# Sheet1chinh_thuc_2.net
KiCad netlist of a schematic drawn in Altium Designer
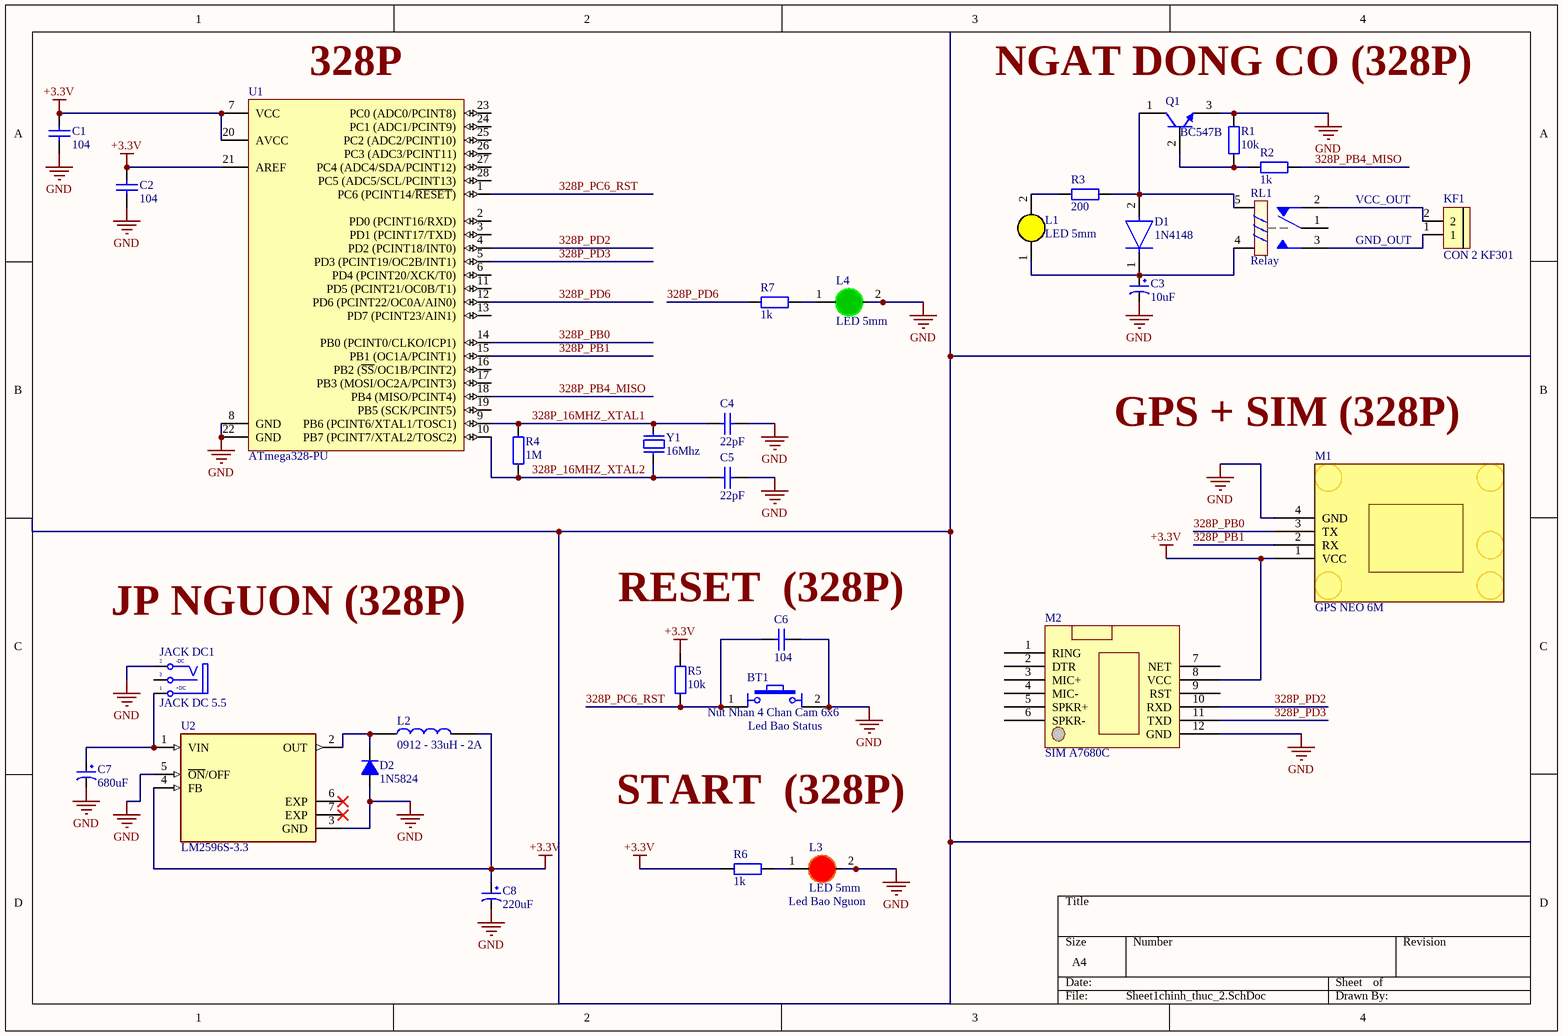
[diagram p0: Sheet1chinh_thuc_2.SchDoc]

(export (version "E")
  (design (tool "Eeschema 10.0.6"))
  (components
    (comp (ref "BT1")
      (value "Nut Nhan 4 Chan Cam 6x6")
      (footprint "Nut Nhan 4 Chan Cam 6x6")
      (description "Nut Nhan 4 Chan 6x6mm")
      (libsource (lib "Altium_Lib_by_KhueNguyenCreator") (part "Nut Nhan 4 Chan Cam 6x6"))
    )
    (comp (ref "C1")
      (value "104")
      (footprint "tu gom")
      (description "Cắm")
      (libsource (lib "Altium_Lib_by_KhueNguyenCreator") (part "Tu gom 104 50V"))
    )
    (comp (ref "C2")
      (value "104")
      (footprint "tu gom")
      (description "Cắm")
      (libsource (lib "Altium_Lib_by_KhueNguyenCreator") (part "Tu gom 104 50V"))
    )
    (comp (ref "C3")
      (value "10uF")
      (footprint "tu hoa 4mm")
      (description "Cắm")
      (libsource (lib "Altium_Lib_by_KhueNguyenCreator") (part "Tu Hoa 10uF 25V 4x7"))
    )
    (comp (ref "C4")
      (value "22pF")
      (footprint "tu gom")
      (description "Cắm")
      (libsource (lib "Altium_Lib_by_KhueNguyenCreator") (part "Tu gom 22pF 50V"))
    )
    (comp (ref "C5")
      (value "22pF")
      (footprint "tu gom")
      (description "Cắm")
      (libsource (lib "Altium_Lib_by_KhueNguyenCreator") (part "Tu gom 22pF 50V"))
    )
    (comp (ref "C6")
      (value "104")
      (footprint "tu gom")
      (description "Cắm")
      (libsource (lib "Altium_Lib_by_KhueNguyenCreator") (part "Tu gom 104 50V"))
    )
    (comp (ref "C7")
      (value "680uF")
      (footprint "tu hoa 13mm")
      (description "Cắm")
      (libsource (lib "Altium_Lib_by_KhueNguyenCreator") (part "Tu Hoa 680uF 25V 13x17"))
    )
    (comp (ref "C8")
      (value "220uF")
      (footprint "Tu hoa 8mm")
      (description "Cắm")
      (libsource (lib "Altium_Lib_by_KhueNguyenCreator") (part "Tu Hoa 220uF 25V 8x10"))
    )
    (comp (ref "D1")
      (value "1N4148")
      (footprint "FP-017AG-MFG")
      (description "DIODE GEN PURP 100V 200MA DO35")
      (fields (field (name "VOLTAGE") "100V"))
      (libsource (lib "Components - 29.11.24 - 08.09") (part "CMP-07163-000046-1"))
    )
    (comp (ref "D2")
      (value "1N5824")
      (footprint "DIODE 0.5A")
      (description "Cắm")
      (libsource (lib "Altium_Lib_by_KhueNguyenCreator") (part "Diode 1N4148"))
    )
    (comp (ref "JACK DC1")
      (value "JACK DC 5.5")
      (footprint "JACK DC 5.5")
      (libsource (lib "Altium_Lib_by_KhueNguyenCreator") (part "JACK DC 5.5"))
    )
    (comp (ref "KF1")
      (value "CON 2 KF301")
      (footprint "Con 2 KF301 5.08")
      (description "Cắm")
      (libsource (lib "Altium_Lib_by_KhueNguyenCreator") (part "CON 2 KF301"))
    )
    (comp (ref "L1")
      (value "LED 5mm")
      (footprint "LED-5MM-Yellow")
      (description "Cắm")
      (libsource (lib "Altium_Lib_by_KhueNguyenCreator") (part "LED 5mm Vang"))
    )
    (comp (ref "L2")
      (value "0912 - 33uH - 2A")
      (footprint "CUON CAM 100uH3A")
      (description "Cắm")
      (libsource (lib "Altium_Lib_by_KhueNguyenCreator") (part "CUON CAM 470uH DIP"))
    )
    (comp (ref "L3")
      (value "LED 5mm")
      (footprint "LED-5MM-RED")
      (description "Cắm")
      (libsource (lib "Altium_Lib_by_KhueNguyenCreator") (part "LED 5mm Do"))
    )
    (comp (ref "L4")
      (value "LED 5mm")
      (footprint "LED-5MM-Green")
      (description "Cắm")
      (libsource (lib "Altium_Lib_by_KhueNguyenCreator") (part "LED 5mm Xanh La"))
    )
    (comp (ref "M1")
      (value "GPS NEO 6M")
      (footprint "PCBComponent_1")
      (libsource (lib "Integrated_Library1") (part "GPS NEO 6M"))
    )
    (comp (ref "M2")
      (value "SIM A7680C")
      (footprint "PCBComponent_1")
      (libsource (lib "Integrated_Library1") (part "SIM A7680C"))
    )
    (comp (ref "Q1")
      (value "BC547B")
      (footprint "ONSC-TO-92-3-29-11")
      (description "Amplifier Transistor, NPN Silicon, 3-Pin TO-92, Bulk Box")
      (fields (field (name "MANUFACTURER") "On Semiconductor"))
      (libsource (lib "Components - 29.11.24 - 08.11") (part "CMP-1048-01467-1"))
    )
    (comp (ref "R1")
      (value "10k")
      (footprint "tro vach 1/2w")
      (description "Cắm")
      (libsource (lib "Altium_Lib_by_KhueNguyenCreator") (part "Tro Vach 1/2W 5% 10k"))
    )
    (comp (ref "R2")
      (value "1k")
      (footprint "tro vach 1/2w")
      (description "Cắm")
      (libsource (lib "Altium_Lib_by_KhueNguyenCreator") (part "Tro Vach 1/2W 5% 1k"))
    )
    (comp (ref "R3")
      (value "200")
      (footprint "tro vach 1/2w")
      (description "Cắm")
      (libsource (lib "Altium_Lib_by_KhueNguyenCreator") (part "Tro Vach 1/2W 5% 150R"))
    )
    (comp (ref "R4")
      (value "1M")
      (footprint "tro vach 1/2w")
      (description "Cắm")
      (libsource (lib "Altium_Lib_by_KhueNguyenCreator") (part "Tro Vach 1/2W 5% 1M"))
    )
    (comp (ref "R5")
      (value "10k")
      (footprint "tro vach 1/2w")
      (description "Cắm")
      (libsource (lib "Altium_Lib_by_KhueNguyenCreator") (part "Tro Vach 1/2W 5% 10k"))
    )
    (comp (ref "R6")
      (value "1k")
      (footprint "tro vach 1/2w")
      (description "Cắm")
      (libsource (lib "Altium_Lib_by_KhueNguyenCreator") (part "Tro Vach 1/2W 5% 1k"))
    )
    (comp (ref "R7")
      (value "1k")
      (footprint "tro vach 1/2w")
      (description "Cắm")
      (libsource (lib "Altium_Lib_by_KhueNguyenCreator") (part "Tro Vach 1/2W 5% 1k"))
    )
    (comp (ref "RL1")
      (value "Relay")
      (footprint "Relay 5 Chan SRD")
      (description "Relay 5 Chan")
      (libsource (lib "Altium_Lib_by_KhueNguyenCreator") (part "Relay 5 Chan SRD"))
    )
    (comp (ref "U1")
      (value "ATmega328-PU")
      (footprint "28P3")
      (libsource (lib "Altium_Lib_by_KhueNguyenCreator") (part "CMP-0095-00015-2"))
    )
    (comp (ref "U2")
      (value "LM2596S-3.3")
      (footprint "VREG_LM2596S-3.3")
      (description "SIMPLE SWITCHER&reg; 4.5V to 40V, 3A Low Component Count Step-Down Regulator 5-DDPAK/TO-263")
      (fields (field (name "MF") "Texas Instruments"))
      (libsource (lib "LM2596S-3.3") (part "LM2596S-3.3"))
    )
    (comp (ref "Y1")
      (value "16Mhz")
      (footprint "Thach Anh 2 chan cam")
      (description "Crystal For all Crystal 2pin.")
      (libsource (lib "Altium_Lib_by_KhueNguyenCreator") (part "Thach Anh 2 chan Cam"))
    )
  )
  (nets
    (net (code "1") (name "+3.3V") (class "Default")
      (node (ref "C1") (pin "1") (pinfunction "1_1") (pintype "passive"))
      (node (ref "C2") (pin "1") (pinfunction "1_1") (pintype "passive"))
      (node (ref "C8") (pin "1") (pinfunction "1_1") (pintype "passive"))
      (node (ref "L2") (pin "2") (pinfunction "2_2") (pintype "passive"))
      (node (ref "M1") (pin "1") (pinfunction "VCC_1") (pintype "passive"))
      (node (ref "M2") (pin "8") (pinfunction "VCC_8") (pintype "passive"))
      (node (ref "R5") (pin "2") (pinfunction "2_2") (pintype "passive"))
      (node (ref "R6") (pin "1") (pinfunction "1_1") (pintype "passive"))
      (node (ref "U1") (pin "20") (pinfunction "AVCC_20") (pintype "power_in"))
      (node (ref "U1") (pin "21") (pinfunction "AREF_21") (pintype "power_in"))
      (node (ref "U1") (pin "7") (pinfunction "VCC_7") (pintype "power_in"))
      (node (ref "U2") (pin "4") (pinfunction "FB_4") (pintype "input"))
    )
    (net (code "2") (name "/328P_16MHZ_XTAL1") (class "Default")
      (node (ref "C4") (pin "2") (pinfunction "2_2") (pintype "passive"))
      (node (ref "R4") (pin "2") (pinfunction "2_2") (pintype "passive"))
      (node (ref "U1") (pin "9") (pinfunction "PB6_(PCINT6/XTAL1/TOSC1)_9") (pintype "bidirectional"))
      (node (ref "Y1") (pin "2") (pinfunction "2_2") (pintype "passive"))
    )
    (net (code "3") (name "/328P_16MHZ_XTAL2") (class "Default")
      (node (ref "C5") (pin "2") (pinfunction "2_2") (pintype "passive"))
      (node (ref "R4") (pin "1") (pinfunction "1_1") (pintype "passive"))
      (node (ref "U1") (pin "10") (pinfunction "PB7_(PCINT7/XTAL2/TOSC2)_10") (pintype "bidirectional"))
      (node (ref "Y1") (pin "1") (pinfunction "1_1") (pintype "passive"))
    )
    (net (code "4") (name "/328P_PB0") (class "Default")
      (node (ref "M1") (pin "3") (pinfunction "TX_3") (pintype "passive"))
      (node (ref "U1") (pin "14") (pinfunction "PB0_(PCINT0/CLKO/ICP1)_14") (pintype "bidirectional"))
    )
    (net (code "5") (name "/328P_PB1") (class "Default")
      (node (ref "M1") (pin "2") (pinfunction "RX_2") (pintype "passive"))
      (node (ref "U1") (pin "15") (pinfunction "PB1_(OC1A/PCINT1)_15") (pintype "bidirectional"))
    )
    (net (code "6") (name "/328P_PB4_MISO") (class "Default")
      (node (ref "R2") (pin "2") (pinfunction "2_2") (pintype "passive"))
      (node (ref "U1") (pin "18") (pinfunction "PB4_(MISO/PCINT4)_18") (pintype "bidirectional"))
    )
    (net (code "7") (name "/328P_PC6_RST") (class "Default")
      (node (ref "BT1") (pin "1") (pintype "passive"))
      (node (ref "C6") (pin "2") (pinfunction "2_2") (pintype "passive"))
      (node (ref "R5") (pin "1") (pinfunction "1_1") (pintype "passive"))
      (node (ref "U1") (pin "1") (pinfunction "PC6_(PCINT14/~{RESET})_1") (pintype "bidirectional"))
    )
    (net (code "8") (name "/328P_PD2") (class "Default")
      (node (ref "M2") (pin "10") (pinfunction "RXD_10") (pintype "passive"))
      (node (ref "U1") (pin "4") (pinfunction "PD2_(PCINT18/INT0)_4") (pintype "bidirectional"))
    )
    (net (code "9") (name "/328P_PD3") (class "Default")
      (node (ref "M2") (pin "11") (pinfunction "TXD_11") (pintype "passive"))
      (node (ref "U1") (pin "5") (pinfunction "PD3_(PCINT19/OC2B/INT1)_5") (pintype "bidirectional"))
    )
    (net (code "10") (name "/328P_PD6") (class "Default")
      (node (ref "R7") (pin "1") (pinfunction "1_1") (pintype "passive"))
      (node (ref "U1") (pin "12") (pinfunction "PD6_(PCINT22/OC0A/AIN0)_12") (pintype "bidirectional"))
    )
    (net (code "11") (name "GND") (class "Default")
      (node (ref "BT1") (pin "2") (pintype "passive"))
      (node (ref "C1") (pin "2") (pinfunction "2_2") (pintype "passive"))
      (node (ref "C2") (pin "2") (pinfunction "2_2") (pintype "passive"))
      (node (ref "C3") (pin "2") (pinfunction "2_2") (pintype "passive"))
      (node (ref "C4") (pin "1") (pinfunction "1_1") (pintype "passive"))
      (node (ref "C5") (pin "1") (pinfunction "1_1") (pintype "passive"))
      (node (ref "C6") (pin "1") (pinfunction "1_1") (pintype "passive"))
      (node (ref "C7") (pin "2") (pinfunction "2_2") (pintype "passive"))
      (node (ref "C8") (pin "2") (pinfunction "2_2") (pintype "passive"))
      (node (ref "D2") (pin "1") (pinfunction "A_1") (pintype "passive"))
      (node (ref "JACK DC1") (pin "2") (pinfunction "TN_2") (pintype "passive"))
      (node (ref "L3") (pin "2") (pinfunction "K_2") (pintype "passive"))
      (node (ref "L4") (pin "2") (pinfunction "K_2") (pintype "passive"))
      (node (ref "M1") (pin "4") (pinfunction "GND_4") (pintype "passive"))
      (node (ref "M2") (pin "12") (pinfunction "GND_12") (pintype "passive"))
      (node (ref "Q1") (pin "3") (pinfunction "E_3") (pintype "passive"))
      (node (ref "R1") (pin "2") (pinfunction "2_2") (pintype "passive"))
      (node (ref "U1") (pin "22") (pinfunction "GND_22") (pintype "power_in"))
      (node (ref "U1") (pin "8") (pinfunction "GND_8") (pintype "power_in"))
      (node (ref "U2") (pin "3") (pinfunction "GND_3") (pintype "power_in"))
      (node (ref "U2") (pin "5") (pinfunction "~{ON}/OFF_5") (pintype "input"))
    )
    (net (code "12") (name "Net-(D1-A)") (class "Default")
      (node (ref "D1") (pin "2") (pinfunction "A_2") (pintype "passive"))
      (node (ref "Q1") (pin "1") (pinfunction "C_1") (pintype "passive"))
      (node (ref "R3") (pin "2") (pinfunction "2_2") (pintype "passive"))
      (node (ref "RL1") (pin "5") (pinfunction "5_5") (pintype "passive"))
    )
    (net (code "13") (name "Net-(D1-C)") (class "Default")
      (node (ref "C3") (pin "1") (pinfunction "1_1") (pintype "passive"))
      (node (ref "D1") (pin "1") (pinfunction "C_1") (pintype "passive"))
      (node (ref "L1") (pin "1") (pinfunction "A_1") (pintype "passive"))
      (node (ref "RL1") (pin "4") (pinfunction "4_4") (pintype "passive"))
    )
    (net (code "14") (name "Net-(D2-K)") (class "Default")
      (node (ref "D2") (pin "2") (pinfunction "K_2") (pintype "passive"))
      (node (ref "L2") (pin "1") (pinfunction "1_1") (pintype "passive"))
      (node (ref "U2") (pin "2") (pinfunction "OUT_2") (pintype "output"))
    )
    (net (code "15") (name "Net-(JACK DC1-T)") (class "Default")
      (node (ref "C7") (pin "1") (pinfunction "1_1") (pintype "passive"))
      (node (ref "JACK DC1") (pin "1") (pinfunction "T_1") (pintype "passive"))
      (node (ref "U2") (pin "1") (pinfunction "VIN_1") (pintype "input"))
    )
    (net (code "16") (name "Net-(KF1-Pad1)") (class "Default")
      (node (ref "KF1") (pin "1") (pinfunction "1_1") (pintype "passive"))
      (node (ref "RL1") (pin "3") (pinfunction "3_3") (pintype "passive"))
    )
    (net (code "17") (name "Net-(KF1-Pad2)") (class "Default")
      (node (ref "KF1") (pin "2") (pinfunction "2_2") (pintype "passive"))
      (node (ref "RL1") (pin "2") (pinfunction "2_2") (pintype "passive"))
    )
    (net (code "18") (name "Net-(L1-K)") (class "Default")
      (node (ref "L1") (pin "2") (pinfunction "K_2") (pintype "passive"))
      (node (ref "R3") (pin "1") (pinfunction "1_1") (pintype "passive"))
    )
    (net (code "19") (name "Net-(L3-A)") (class "Default")
      (node (ref "L3") (pin "1") (pinfunction "A_1") (pintype "passive"))
      (node (ref "R6") (pin "2") (pinfunction "2_2") (pintype "passive"))
    )
    (net (code "20") (name "Net-(L4-A)") (class "Default")
      (node (ref "L4") (pin "1") (pinfunction "A_1") (pintype "passive"))
      (node (ref "R7") (pin "2") (pinfunction "2_2") (pintype "passive"))
    )
    (net (code "21") (name "Net-(Q1-B)") (class "Default")
      (node (ref "Q1") (pin "2") (pinfunction "B_2") (pintype "passive"))
      (node (ref "R1") (pin "1") (pinfunction "1_1") (pintype "passive"))
      (node (ref "R2") (pin "1") (pinfunction "1_1") (pintype "passive"))
    )
    (net (code "22") (name "unconnected-(JACK DC1-S-Pad3)") (class "Default")
      (node (ref "JACK DC1") (pin "3") (pinfunction "S_3") (pintype "power_in"))
    )
    (net (code "23") (name "unconnected-(M2-DTR-Pad2)") (class "Default")
      (node (ref "M2") (pin "2") (pinfunction "DTR_2") (pintype "passive"))
    )
    (net (code "24") (name "unconnected-(M2-MIC+-Pad3)") (class "Default")
      (node (ref "M2") (pin "3") (pinfunction "MIC+_3") (pintype "passive"))
    )
    (net (code "25") (name "unconnected-(M2-MIC--Pad4)") (class "Default")
      (node (ref "M2") (pin "4") (pinfunction "MIC-_4") (pintype "passive"))
    )
    (net (code "26") (name "unconnected-(M2-NET-Pad7)") (class "Default")
      (node (ref "M2") (pin "7") (pinfunction "NET_7") (pintype "passive"))
    )
    (net (code "27") (name "unconnected-(M2-RING-Pad1)") (class "Default")
      (node (ref "M2") (pin "1") (pinfunction "RING_1") (pintype "passive"))
    )
    (net (code "28") (name "unconnected-(M2-RST-Pad9)") (class "Default")
      (node (ref "M2") (pin "9") (pinfunction "RST_9") (pintype "passive"))
    )
    (net (code "29") (name "unconnected-(M2-SPKR+-Pad5)") (class "Default")
      (node (ref "M2") (pin "5") (pinfunction "SPKR+_5") (pintype "passive"))
    )
    (net (code "30") (name "unconnected-(M2-SPKR--Pad6)") (class "Default")
      (node (ref "M2") (pin "6") (pinfunction "SPKR-_6") (pintype "passive"))
    )
    (net (code "31") (name "unconnected-(RL1-Pad1)") (class "Default")
      (node (ref "RL1") (pin "1") (pinfunction "1_1") (pintype "passive"))
    )
    (net (code "32") (name "unconnected-(U1-PB2_(~{SS}{slash}OC1B{slash}PCINT2)-Pad16)") (class "Default")
      (node (ref "U1") (pin "16") (pinfunction "PB2_(~{SS}/OC1B/PCINT2)_16") (pintype "bidirectional"))
    )
    (net (code "33") (name "unconnected-(U1-PB3_(MOSI{slash}OC2A{slash}PCINT3)-Pad17)") (class "Default")
      (node (ref "U1") (pin "17") (pinfunction "PB3_(MOSI/OC2A/PCINT3)_17") (pintype "bidirectional"))
    )
    (net (code "34") (name "unconnected-(U1-PB5_(SCK{slash}PCINT5)-Pad19)") (class "Default")
      (node (ref "U1") (pin "19") (pinfunction "PB5_(SCK/PCINT5)_19") (pintype "bidirectional"))
    )
    (net (code "35") (name "unconnected-(U1-PC0_(ADC0{slash}PCINT8)-Pad23)") (class "Default")
      (node (ref "U1") (pin "23") (pinfunction "PC0_(ADC0/PCINT8)_23") (pintype "bidirectional"))
    )
    (net (code "36") (name "unconnected-(U1-PC1_(ADC1{slash}PCINT9)-Pad24)") (class "Default")
      (node (ref "U1") (pin "24") (pinfunction "PC1_(ADC1/PCINT9)_24") (pintype "bidirectional"))
    )
    (net (code "37") (name "unconnected-(U1-PC2_(ADC2{slash}PCINT10)-Pad25)") (class "Default")
      (node (ref "U1") (pin "25") (pinfunction "PC2_(ADC2/PCINT10)_25") (pintype "bidirectional"))
    )
    (net (code "38") (name "unconnected-(U1-PC3_(ADC3{slash}PCINT11)-Pad26)") (class "Default")
      (node (ref "U1") (pin "26") (pinfunction "PC3_(ADC3/PCINT11)_26") (pintype "bidirectional"))
    )
    (net (code "39") (name "unconnected-(U1-PC4_(ADC4{slash}SDA{slash}PCINT12)-Pad27)") (class "Default")
      (node (ref "U1") (pin "27") (pinfunction "PC4_(ADC4/SDA/PCINT12)_27") (pintype "bidirectional"))
    )
    (net (code "40") (name "unconnected-(U1-PC5_(ADC5{slash}SCL{slash}PCINT13)-Pad28)") (class "Default")
      (node (ref "U1") (pin "28") (pinfunction "PC5_(ADC5/SCL/PCINT13)_28") (pintype "bidirectional"))
    )
    (net (code "41") (name "unconnected-(U1-PD0_(PCINT16{slash}RXD)-Pad2)") (class "Default")
      (node (ref "U1") (pin "2") (pinfunction "PD0_(PCINT16/RXD)_2") (pintype "bidirectional"))
    )
    (net (code "42") (name "unconnected-(U1-PD1_(PCINT17{slash}TXD)-Pad3)") (class "Default")
      (node (ref "U1") (pin "3") (pinfunction "PD1_(PCINT17/TXD)_3") (pintype "bidirectional"))
    )
    (net (code "43") (name "unconnected-(U1-PD4_(PCINT20{slash}XCK{slash}T0)-Pad6)") (class "Default")
      (node (ref "U1") (pin "6") (pinfunction "PD4_(PCINT20/XCK/T0)_6") (pintype "bidirectional"))
    )
    (net (code "44") (name "unconnected-(U1-PD5_(PCINT21{slash}OC0B{slash}T1)-Pad11)") (class "Default")
      (node (ref "U1") (pin "11") (pinfunction "PD5_(PCINT21/OC0B/T1)_11") (pintype "bidirectional"))
    )
    (net (code "45") (name "unconnected-(U1-PD7_(PCINT23{slash}AIN1)-Pad13)") (class "Default")
      (node (ref "U1") (pin "13") (pinfunction "PD7_(PCINT23/AIN1)_13") (pintype "bidirectional"))
    )
    (net (code "46") (name "unconnected-(U2-EXP-Pad6)") (class "Default")
      (node (ref "U2") (pin "6") (pinfunction "EXP_6") (pintype "power_in+no_connect"))
    )
    (net (code "47") (name "unconnected-(U2-EXP-Pad7)") (class "Default")
      (node (ref "U2") (pin "7") (pinfunction "EXP_7") (pintype "power_in+no_connect"))
    )
  )
)
